# EasyEDA_ATTinyX5_ICSP_V1_Schematic.net
KiCad netlist of a schematic drawn in EasyEDA
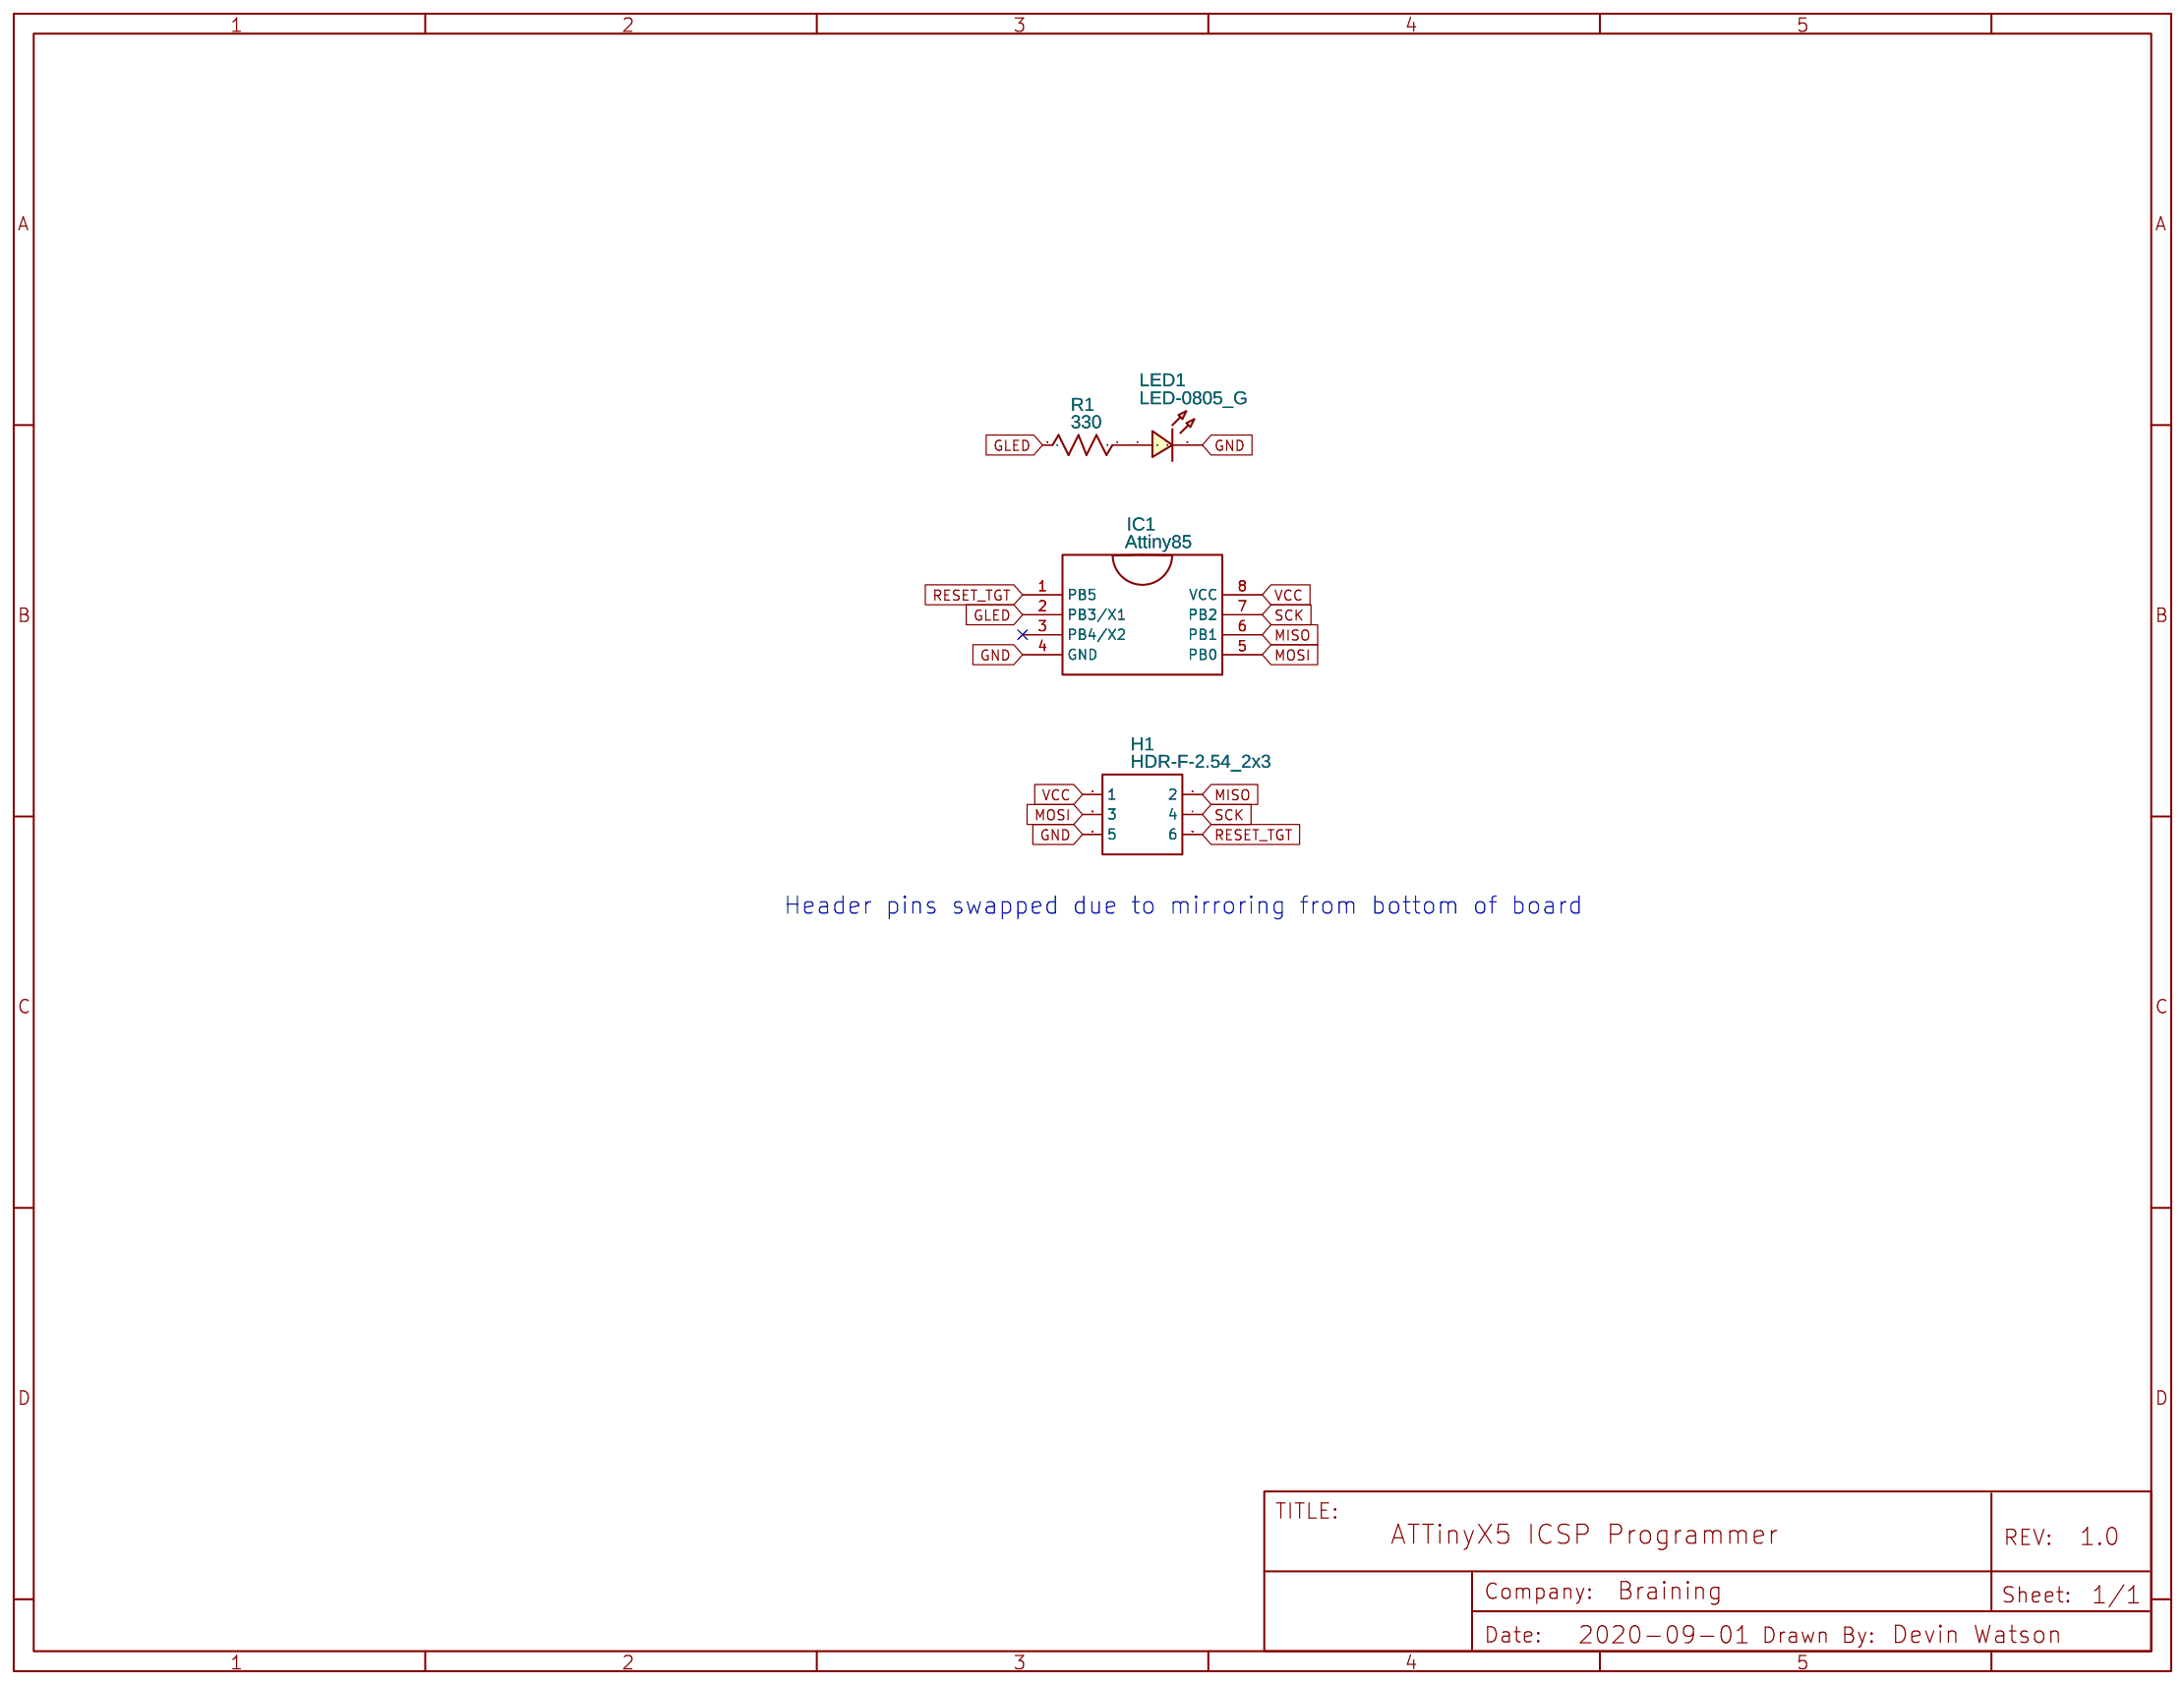
[diagram p0: schematic sheet]

(export (version "E")
  (design (tool "Eeschema 10.0.6"))
  (components
    (comp (ref "H1")
      (value "HDR-F-2.54_2x3")
      (fields (field (name "BOM_Supplier Part") "C65114"))
      (libsource (lib "") (part "HDR-F-2.54_2x3"))
    )
    (comp (ref "IC1") (value "Attiny85") (libsource (lib "") (part "Attiny85")))
    (comp (ref "LED1")
      (value "LED-0805_G")
      (fields
        (field (name "BOM_Manufacturer Part") "17-21SYGC/S530-E2/TR8")
        (field (name "BOM_Supplier Part") "638-1721SYGCS530E2")
      )
      (libsource (lib "") (part "LED-0805_G"))
    )
    (comp (ref "R1")
      (value "330")
      (fields
        (field (name "BOM_Manufacturer Part") "CRCW0805330RJNEAC")
        (field (name "BOM_Supplier Part") "71-CRCW0805330RJNEAC")
      )
      (libsource (lib "") (part "R_0805_US"))
    )
  )
  (nets
    (net (code "1") (name "GLED") (class "Default")
      (node (ref "IC1") (pin "2") (pinfunction "PB3/X1_2") (pintype "bidirectional"))
      (node (ref "R1") (pin "1") (pinfunction "1_1") (pintype "unspecified"))
    )
    (net (code "2") (name "GND") (class "Default")
      (node (ref "H1") (pin "5") (pinfunction "5_5") (pintype "input"))
      (node (ref "IC1") (pin "4") (pinfunction "GND_4") (pintype "passive"))
      (node (ref "LED1") (pin "2") (pinfunction "2_2") (pintype "unspecified"))
    )
    (net (code "3") (name "MISO") (class "Default")
      (node (ref "H1") (pin "2") (pinfunction "2_2") (pintype "input"))
      (node (ref "IC1") (pin "6") (pinfunction "PB1_6") (pintype "bidirectional"))
    )
    (net (code "4") (name "MOSI") (class "Default")
      (node (ref "H1") (pin "3") (pinfunction "3_3") (pintype "input"))
      (node (ref "IC1") (pin "5") (pinfunction "PB0_5") (pintype "bidirectional"))
    )
    (net (code "5") (name "Net-(LED1-Pad1)") (class "Default")
      (node (ref "LED1") (pin "1") (pinfunction "1_1") (pintype "unspecified"))
      (node (ref "R1") (pin "2") (pinfunction "2_2") (pintype "unspecified"))
    )
    (net (code "6") (name "RESET_TGT") (class "Default")
      (node (ref "H1") (pin "6") (pinfunction "6_6") (pintype "input"))
      (node (ref "IC1") (pin "1") (pinfunction "PB5_1") (pintype "bidirectional"))
    )
    (net (code "7") (name "SCK") (class "Default")
      (node (ref "H1") (pin "4") (pinfunction "4_4") (pintype "input"))
      (node (ref "IC1") (pin "7") (pinfunction "PB2_7") (pintype "bidirectional"))
    )
    (net (code "8") (name "VCC") (class "Default")
      (node (ref "H1") (pin "1") (pinfunction "1_1") (pintype "input"))
      (node (ref "IC1") (pin "8") (pinfunction "VCC_8") (pintype "passive"))
    )
    (net (code "9") (name "unconnected-(IC1-PB4{slash}X2-Pad3)") (class "Default")
      (node (ref "IC1") (pin "3") (pinfunction "PB4/X2_3") (pintype "bidirectional+no_connect"))
    )
  )
)
